# SimpleSwitch.net
KiCad netlist of a schematic drawn in EAGLE
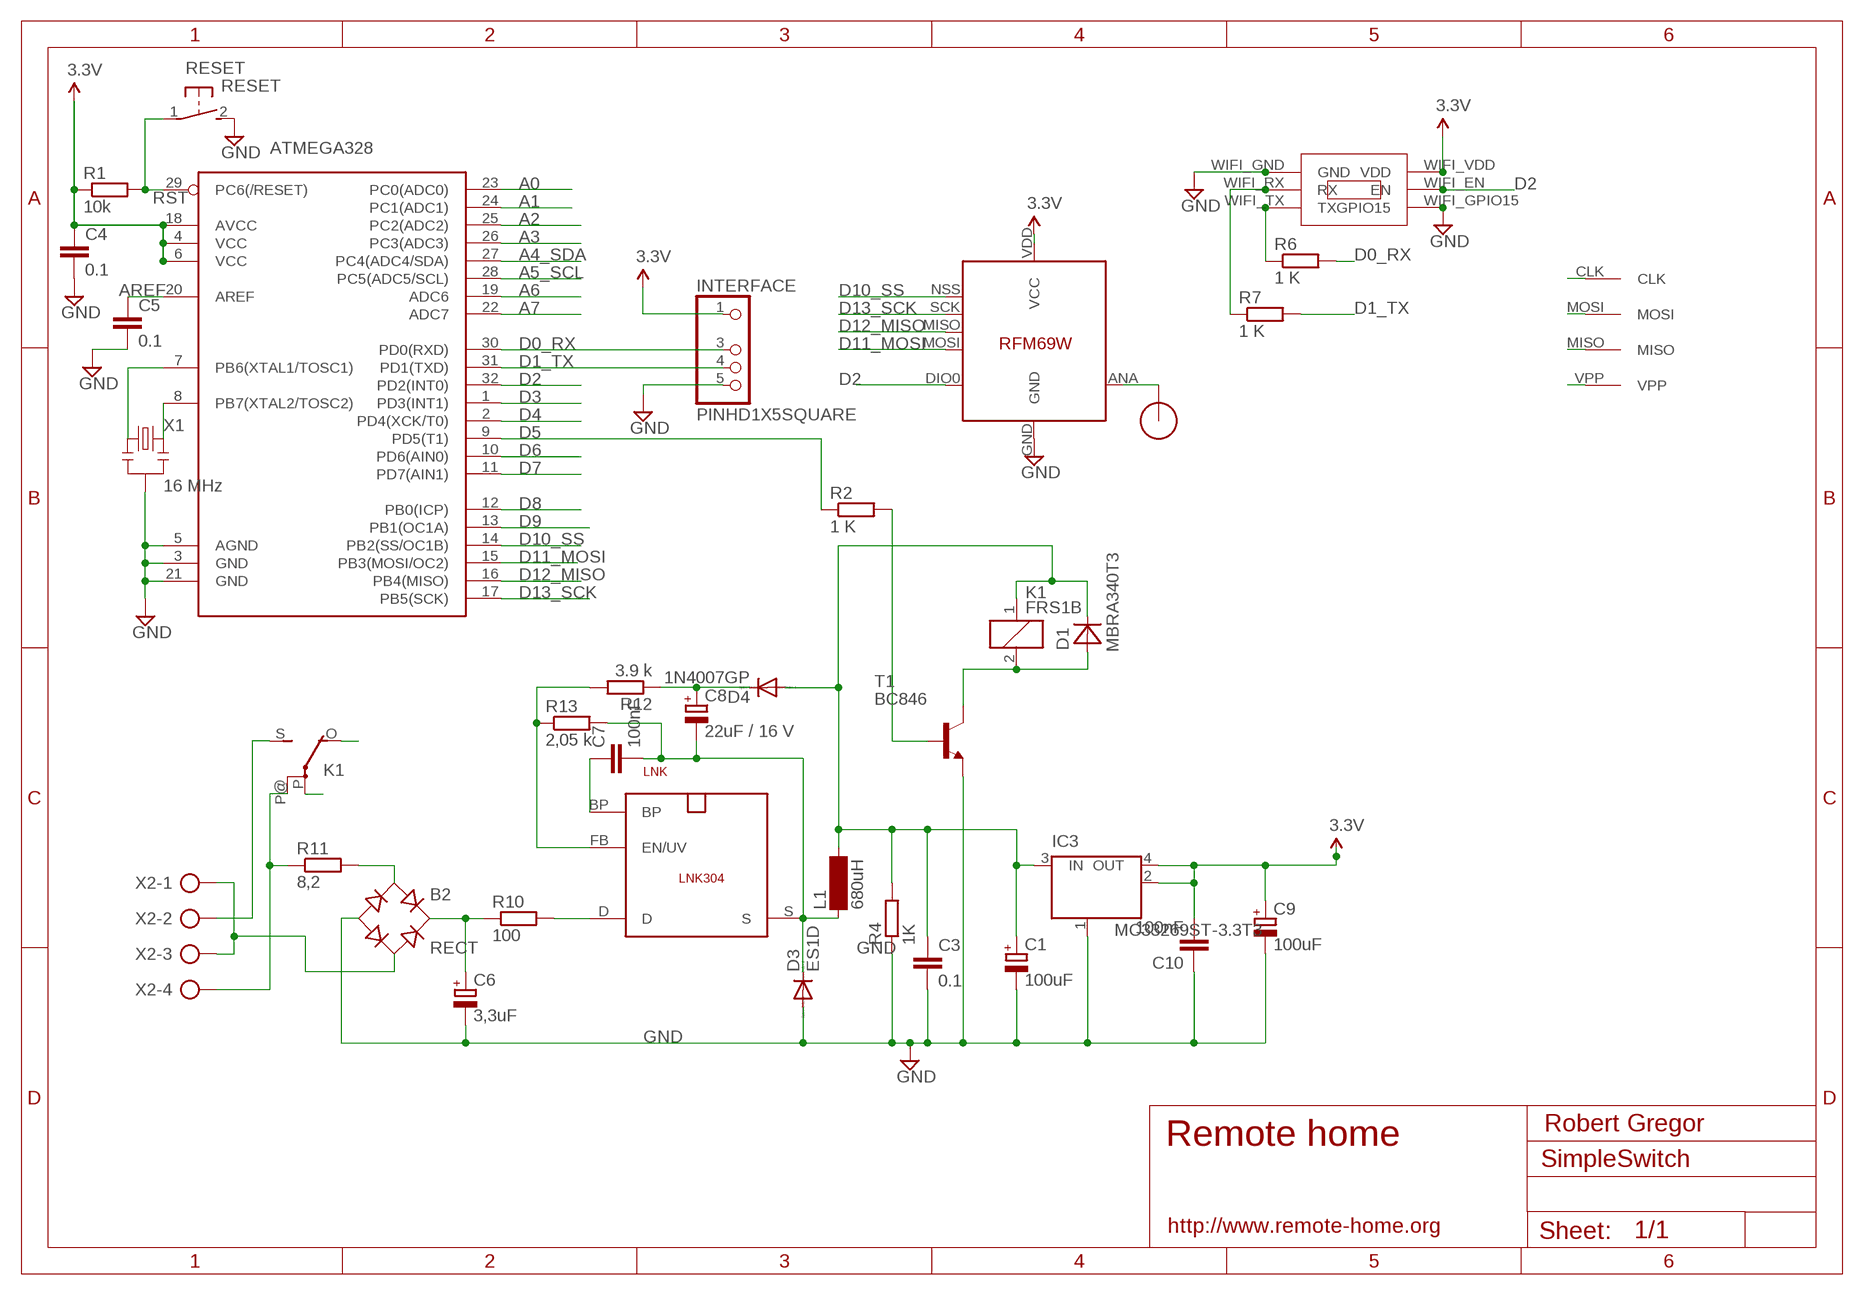
[diagram p0: schematic, sheet 1]

(export (version "E")
  (design (tool "Eeschema 10.0.6"))
  (components
    (comp (ref "ATMEGA328")
      (value "ATMega-328")
      (footprint "eagle-import:TQFP32-08")
      (libsource (lib "eagle-import") (part "ATMEGA168/328TQFP32"))
    )
    (comp (ref "B2")
      (value "RECT")
      (footprint "eagle-import:TO-269AA")
      (libsource (lib "eagle-import") (part "RECTIFIER-S40"))
    )
    (comp (ref "C1")
      (value "100uF")
      (footprint "eagle-import:SMC_B")
      (libsource (lib "eagle-import") (part "CPOL-EUSMCB"))
    )
    (comp (ref "C3")
      (value "0.1")
      (footprint "eagle-import:C2012")
      (libsource (lib "eagle-import") (part "C-EUC2012"))
    )
    (comp (ref "C4")
      (value "0.1")
      (footprint "eagle-import:C2012")
      (libsource (lib "eagle-import") (part "C-EUC2012"))
    )
    (comp (ref "C5")
      (value "0.1")
      (footprint "eagle-import:C2012")
      (libsource (lib "eagle-import") (part "C-EUC2012"))
    )
    (comp (ref "C6")
      (value "3,3uF")
      (footprint "eagle-import:E5-10,5")
      (libsource (lib "eagle-import") (part "CPOL-EUE5-10.5"))
    )
    (comp (ref "C7")
      (value "100nF")
      (footprint "eagle-import:C2012")
      (libsource (lib "eagle-import") (part "C-EUC2012"))
    )
    (comp (ref "C8")
      (value "22uF / 16 V")
      (footprint "eagle-import:SMC_C")
      (libsource (lib "eagle-import") (part "CPOL-EUSMCC"))
    )
    (comp (ref "C9")
      (value "100uF")
      (footprint "eagle-import:SMC_B")
      (libsource (lib "eagle-import") (part "CPOL-EUSMCB"))
    )
    (comp (ref "C10")
      (value "100nF")
      (footprint "eagle-import:C2012")
      (libsource (lib "eagle-import") (part "C-EUC2012"))
    )
    (comp (ref "D1")
      (value "MBRA340T3")
      (footprint "eagle-import:SMA")
      (libsource (lib "eagle-import") (part "MBRA340T3"))
    )
    (comp (ref "D3")
      (value "ES1D")
      (footprint "eagle-import:DO214AC")
      (libsource (lib "eagle-import") (part "DIODE-DO214AC"))
    )
    (comp (ref "D4")
      (value "1N4007GP")
      (footprint "eagle-import:DO214AA")
      (libsource (lib "eagle-import") (part "DIODE-DO214AA"))
    )
    (comp (ref "IC3")
      (value "MC33269ST-3.3T3")
      (footprint "eagle-import:SOT223")
      (libsource (lib "eagle-import") (part "MC33269ST-3.3T3"))
    )
    (comp (ref "INTERFACE")
      (value "PINHD1X5SQUARE")
      (footprint "eagle-import:PINHD1X05-SQUARE")
      (libsource (lib "eagle-import") (part "PINHD1X5SQUARE"))
    )
    (comp (ref "K1")
      (value "FRS1B")
      (footprint "eagle-import:FRS1B")
      (libsource (lib "eagle-import") (part "FRS1B"))
    )
    (comp (ref "L1")
      (value "680uH")
      (footprint "eagle-import:BS11")
      (libsource (lib "eagle-import") (part "BS11"))
    )
    (comp (ref "LNK")
      (value "LNK304")
      (footprint "eagle-import:SO-8C")
      (libsource (lib "eagle-import") (part "SO-8C"))
    )
    (comp (ref "R1")
      (value "10k")
      (footprint "eagle-import:R2012")
      (libsource (lib "eagle-import") (part "R-EU_R2012"))
    )
    (comp (ref "R2")
      (value "1 K")
      (footprint "eagle-import:M2012")
      (libsource (lib "eagle-import") (part "R-EU_M2012"))
    )
    (comp (ref "R4")
      (value "1K")
      (footprint "eagle-import:M2012")
      (libsource (lib "eagle-import") (part "R-EU_M2012"))
    )
    (comp (ref "R6")
      (value "1 K")
      (footprint "eagle-import:M2012")
      (libsource (lib "eagle-import") (part "R-EU_M2012"))
    )
    (comp (ref "R7")
      (value "1 K")
      (footprint "eagle-import:M2012")
      (libsource (lib "eagle-import") (part "R-EU_M2012"))
    )
    (comp (ref "R10")
      (value "100")
      (footprint "eagle-import:R2512W")
      (libsource (lib "eagle-import") (part "R-EU_R2512W"))
    )
    (comp (ref "R11")
      (value "8,2")
      (footprint "eagle-import:0411_12")
      (libsource (lib "eagle-import") (part "R-EU_0411/12"))
    )
    (comp (ref "R12")
      (value "3.9 k")
      (footprint "eagle-import:M2012")
      (libsource (lib "eagle-import") (part "R-EU_M2012"))
    )
    (comp (ref "R13")
      (value "2,05 k")
      (footprint "eagle-import:M2012")
      (libsource (lib "eagle-import") (part "R-EU_M2012"))
    )
    (comp (ref "RESET")
      (value "RESET")
      (footprint "eagle-import:DTSM-3")
      (libsource (lib "eagle-import") (part "DTSM-3"))
    )
    (comp (ref "RFM69")
      (value "RFM69W")
      (footprint "eagle-import:RFM69W")
      (libsource (lib "eagle-import") (part "RFM69W"))
    )
    (comp (ref "T1")
      (value "BC846")
      (footprint "eagle-import:SOT23")
      (libsource (lib "eagle-import") (part "BC846"))
    )
    (comp (ref "U$1")
      (value "RFM12B_ANTENNA")
      (footprint "eagle-import:RFM12B-ANTENNA")
      (libsource (lib "eagle-import") (part "RFM12B_ANTENNA"))
    )
    (comp (ref "U$2")
      (value "AVRHEADERDIP")
      (footprint "eagle-import:AVRHEADER")
      (libsource (lib "eagle-import") (part "AVRHEADERDIP"))
    )
    (comp (ref "U$5")
      (value "ESP03")
      (footprint "eagle-import:ESP03")
      (libsource (lib "eagle-import") (part "ESP03"))
    )
    (comp (ref "X1")
      (value "16 MHz")
      (footprint "eagle-import:RESONATOR-SMD")
      (libsource (lib "eagle-import") (part "RESONATORSMD"))
    )
    (comp (ref "X2")
      (value "AK500/4")
      (footprint "eagle-import:AK500_4")
      (libsource (lib "eagle-import") (part "AK500/4"))
    )
  )
  (nets
    (net (code "1") (name "/A0") (class "Default")
      (node (ref "ATMEGA328") (pin "23") (pinfunction "PC0(ADC0)_23") (pintype "bidirectional"))
    )
    (net (code "2") (name "/A1") (class "Default")
      (node (ref "ATMEGA328") (pin "24") (pinfunction "PC1(ADC1)_24") (pintype "bidirectional"))
    )
    (net (code "3") (name "/A2") (class "Default")
      (node (ref "ATMEGA328") (pin "25") (pinfunction "PC2(ADC2)_25") (pintype "bidirectional"))
    )
    (net (code "4") (name "/A3") (class "Default")
      (node (ref "ATMEGA328") (pin "26") (pinfunction "PC3(ADC3)_26") (pintype "bidirectional"))
    )
    (net (code "5") (name "/A4_SDA") (class "Default")
      (node (ref "ATMEGA328") (pin "27") (pinfunction "PC4(ADC4/SDA)_27") (pintype "bidirectional"))
    )
    (net (code "6") (name "/A5_SCL") (class "Default")
      (node (ref "ATMEGA328") (pin "28") (pinfunction "PC5(ADC5/SCL)_28") (pintype "bidirectional"))
    )
    (net (code "7") (name "/A6") (class "Default")
      (node (ref "ATMEGA328") (pin "19") (pinfunction "ADC6_19") (pintype "bidirectional"))
    )
    (net (code "8") (name "/A7") (class "Default")
      (node (ref "ATMEGA328") (pin "22") (pinfunction "ADC7_22") (pintype "bidirectional"))
    )
    (net (code "9") (name "/AREF") (class "Default")
      (node (ref "ATMEGA328") (pin "20") (pinfunction "AREF_20") (pintype "bidirectional"))
      (node (ref "C5") (pin "1") (pinfunction "1_1") (pintype "passive"))
    )
    (net (code "10") (name "/D0_RX") (class "Default")
      (node (ref "ATMEGA328") (pin "30") (pinfunction "PD0(RXD)_30") (pintype "bidirectional"))
      (node (ref "INTERFACE") (pin "3") (pinfunction "3_3") (pintype "passive"))
      (node (ref "R6") (pin "2") (pinfunction "2_2") (pintype "passive"))
    )
    (net (code "11") (name "/D1_TX") (class "Default")
      (node (ref "ATMEGA328") (pin "31") (pinfunction "PD1(TXD)_31") (pintype "bidirectional"))
      (node (ref "INTERFACE") (pin "4") (pinfunction "4_4") (pintype "passive"))
      (node (ref "R7") (pin "2") (pinfunction "2_2") (pintype "passive"))
    )
    (net (code "12") (name "/D2") (class "Default")
      (node (ref "ATMEGA328") (pin "32") (pinfunction "PD2(INT0)_32") (pintype "bidirectional"))
      (node (ref "RFM69") (pin "DIO0") (pinfunction "DIO0_DIO0") (pintype "open_collector"))
      (node (ref "U$5") (pin "WIFI_EN") (pinfunction "EN_WIFI_EN") (pintype "input"))
    )
    (net (code "13") (name "/D3") (class "Default")
      (node (ref "ATMEGA328") (pin "1") (pinfunction "PD3(INT1)_1") (pintype "bidirectional"))
    )
    (net (code "14") (name "/D4") (class "Default")
      (node (ref "ATMEGA328") (pin "2") (pinfunction "PD4(XCK/T0)_2") (pintype "bidirectional"))
    )
    (net (code "15") (name "/D5") (class "Default")
      (node (ref "ATMEGA328") (pin "9") (pinfunction "PD5(T1)_9") (pintype "bidirectional"))
      (node (ref "R2") (pin "1") (pinfunction "1_1") (pintype "passive"))
    )
    (net (code "16") (name "/D6") (class "Default")
      (node (ref "ATMEGA328") (pin "10") (pinfunction "PD6(AIN0)_10") (pintype "bidirectional"))
    )
    (net (code "17") (name "/D7") (class "Default")
      (node (ref "ATMEGA328") (pin "11") (pinfunction "PD7(AIN1)_11") (pintype "bidirectional"))
    )
    (net (code "18") (name "/D8") (class "Default")
      (node (ref "ATMEGA328") (pin "12") (pinfunction "PB0(ICP)_12") (pintype "bidirectional"))
    )
    (net (code "19") (name "/D9") (class "Default")
      (node (ref "ATMEGA328") (pin "13") (pinfunction "PB1(OC1A)_13") (pintype "bidirectional"))
    )
    (net (code "20") (name "/D10_SS") (class "Default")
      (node (ref "ATMEGA328") (pin "14") (pinfunction "PB2(SS/OC1B)_14") (pintype "bidirectional"))
      (node (ref "RFM69") (pin "NSS") (pinfunction "SEL_NSS") (pintype "input"))
    )
    (net (code "21") (name "/D11_MOSI") (class "Default")
      (node (ref "ATMEGA328") (pin "15") (pinfunction "PB3(MOSI/OC2)_15") (pintype "bidirectional"))
      (node (ref "RFM69") (pin "MOSI") (pinfunction "MOSI_MOSI") (pintype "output"))
      (node (ref "U$2") (pin "MOSI") (pinfunction "MOSI_MOSI") (pintype "bidirectional"))
    )
    (net (code "22") (name "/D12_MISO") (class "Default")
      (node (ref "ATMEGA328") (pin "16") (pinfunction "PB4(MISO)_16") (pintype "bidirectional"))
      (node (ref "RFM69") (pin "MISO") (pinfunction "MISO_MISO") (pintype "input"))
      (node (ref "U$2") (pin "MISO") (pinfunction "MISO_MISO") (pintype "bidirectional"))
    )
    (net (code "23") (name "/D13_SCK") (class "Default")
      (node (ref "ATMEGA328") (pin "17") (pinfunction "PB5(SCK)_17") (pintype "bidirectional"))
      (node (ref "RFM69") (pin "SCK") (pinfunction "SCK_SCK") (pintype "input"))
      (node (ref "U$2") (pin "CLK") (pinfunction "CLK_CLK") (pintype "bidirectional"))
    )
    (net (code "24") (name "/RST") (class "Default")
      (node (ref "ATMEGA328") (pin "29") (pinfunction "PC6(/RESET)_29") (pintype "bidirectional"))
      (node (ref "R1") (pin "2") (pinfunction "2_2") (pintype "passive"))
      (node (ref "RESET") (pin "1") (pinfunction "1_1") (pintype "passive"))
      (node (ref "U$2") (pin "VPP") (pinfunction "VPP_VPP") (pintype "bidirectional"))
    )
    (net (code "25") (name "3.3V") (class "Default")
      (node (ref "ATMEGA328") (pin "18") (pinfunction "AVCC_18") (pintype "bidirectional"))
      (node (ref "ATMEGA328") (pin "4") (pinfunction "VCC_4") (pintype "bidirectional"))
      (node (ref "ATMEGA328") (pin "6") (pinfunction "VCC_6") (pintype "bidirectional"))
      (node (ref "C10") (pin "2") (pinfunction "2_2") (pintype "passive"))
      (node (ref "C4") (pin "1") (pinfunction "1_1") (pintype "passive"))
      (node (ref "C9") (pin "+") (pinfunction "+_+") (pintype "passive"))
      (node (ref "IC3") (pin "2") (pinfunction "OUT_2") (pintype "passive"))
      (node (ref "IC3") (pin "4") (pinfunction "OUT_4") (pintype "passive"))
      (node (ref "INTERFACE") (pin "1") (pinfunction "1_1") (pintype "passive"))
      (node (ref "R1") (pin "1") (pinfunction "1_1") (pintype "passive"))
      (node (ref "RFM69") (pin "VDD") (pinfunction "VCC_VDD") (pintype "power_in"))
      (node (ref "U$5") (pin "WIFI_VDD") (pinfunction "VDD_WIFI_VDD") (pintype "power_in"))
    )
    (net (code "26") (name "GND") (class "Default")
      (node (ref "ATMEGA328") (pin "21") (pinfunction "GND_21") (pintype "bidirectional"))
      (node (ref "ATMEGA328") (pin "3") (pinfunction "GND_3") (pintype "bidirectional"))
      (node (ref "ATMEGA328") (pin "5") (pinfunction "AGND_5") (pintype "bidirectional"))
      (node (ref "B2") (pin "-") (pinfunction "-_-") (pintype "passive"))
      (node (ref "C1") (pin "-") (pinfunction "-_-") (pintype "passive"))
      (node (ref "C10") (pin "1") (pinfunction "1_1") (pintype "passive"))
      (node (ref "C3") (pin "2") (pinfunction "2_2") (pintype "passive"))
      (node (ref "C4") (pin "2") (pinfunction "2_2") (pintype "passive"))
      (node (ref "C5") (pin "2") (pinfunction "2_2") (pintype "passive"))
      (node (ref "C6") (pin "-") (pinfunction "-_-") (pintype "passive"))
      (node (ref "C9") (pin "-") (pinfunction "-_-") (pintype "passive"))
      (node (ref "D3") (pin "A") (pinfunction "A_A") (pintype "passive"))
      (node (ref "IC3") (pin "1") (pinfunction "GND/ADJ_1") (pintype "input"))
      (node (ref "INTERFACE") (pin "5") (pinfunction "5_5") (pintype "passive"))
      (node (ref "R4") (pin "1") (pinfunction "1_1") (pintype "passive"))
      (node (ref "RESET") (pin "2") (pinfunction "2_2") (pintype "passive"))
      (node (ref "RFM69") (pin "GND") (pinfunction "GND_GND") (pintype "power_in"))
      (node (ref "T1") (pin "2") (pinfunction "E_2") (pintype "passive"))
      (node (ref "U$5") (pin "WIFI_GND") (pinfunction "GND_WIFI_GND") (pintype "power_in"))
      (node (ref "U$5") (pin "WIFI_GPIO15") (pinfunction "GPIO15_WIFI_GPIO15") (pintype "input"))
      (node (ref "X1") (pin "2") (pinfunction "2_2") (pintype "passive"))
    )
    (net (code "27") (name "Net-(ATMEGA328-PB6(XTAL1{slash}TOSC1))") (class "Default")
      (node (ref "ATMEGA328") (pin "7") (pinfunction "PB6(XTAL1/TOSC1)_7") (pintype "bidirectional"))
      (node (ref "X1") (pin "1") (pinfunction "1_1") (pintype "passive"))
    )
    (net (code "28") (name "Net-(ATMEGA328-PB7(XTAL2{slash}TOSC2))") (class "Default")
      (node (ref "ATMEGA328") (pin "8") (pinfunction "PB7(XTAL2/TOSC2)_8") (pintype "bidirectional"))
      (node (ref "X1") (pin "3") (pinfunction "3_3") (pintype "passive"))
    )
    (net (code "29") (name "Net-(B2-Pad+)") (class "Default")
      (node (ref "B2") (pin "+") (pinfunction "+_+") (pintype "passive"))
      (node (ref "C6") (pin "+") (pinfunction "+_+") (pintype "passive"))
      (node (ref "R10") (pin "1") (pinfunction "1_1") (pintype "passive"))
    )
    (net (code "30") (name "Net-(B2-PadAC1)") (class "Default")
      (node (ref "B2") (pin "AC1") (pinfunction "AC1_AC1") (pintype "passive"))
      (node (ref "R11") (pin "2") (pinfunction "2_2") (pintype "passive"))
    )
    (net (code "31") (name "Net-(C7-Pad1)") (class "Default")
      (node (ref "C7") (pin "1") (pinfunction "1_1") (pintype "passive"))
      (node (ref "LNK") (pin "BP") (pinfunction "BP_BP") (pintype "passive"))
    )
    (net (code "32") (name "Net-(C7-Pad2)") (class "Default")
      (node (ref "C7") (pin "2") (pinfunction "2_2") (pintype "passive"))
      (node (ref "C8") (pin "-") (pinfunction "-_-") (pintype "passive"))
      (node (ref "D3") (pin "C") (pinfunction "C_C") (pintype "passive"))
      (node (ref "L1") (pin "1") (pinfunction "1_1") (pintype "passive"))
      (node (ref "LNK") (pin "S") (pinfunction "S_S") (pintype "power_in"))
      (node (ref "R13") (pin "2") (pinfunction "2_2") (pintype "passive"))
    )
    (net (code "33") (name "Net-(C8-Pad+)") (class "Default")
      (node (ref "C8") (pin "+") (pinfunction "+_+") (pintype "passive"))
      (node (ref "D4") (pin "C") (pinfunction "C_C") (pintype "passive"))
      (node (ref "R12") (pin "1") (pinfunction "1_1") (pintype "passive"))
    )
    (net (code "34") (name "Net-(IC3-IN)") (class "Default")
      (node (ref "C1") (pin "+") (pinfunction "+_+") (pintype "passive"))
      (node (ref "C3") (pin "1") (pinfunction "1_1") (pintype "passive"))
      (node (ref "D1") (pin "C") (pinfunction "C_C") (pintype "passive"))
      (node (ref "D4") (pin "A") (pinfunction "A_A") (pintype "passive"))
      (node (ref "IC3") (pin "3") (pinfunction "IN_3") (pintype "input"))
      (node (ref "K1") (pin "1") (pinfunction "1_1") (pintype "passive"))
      (node (ref "L1") (pin "2") (pinfunction "2_2") (pintype "passive"))
      (node (ref "R4") (pin "2") (pinfunction "2_2") (pintype "passive"))
    )
    (net (code "35") (name "Net-(LNK-EN{slash}UV)") (class "Default")
      (node (ref "LNK") (pin "FB") (pinfunction "EN/UV_FB") (pintype "input"))
      (node (ref "R12") (pin "2") (pinfunction "2_2") (pintype "passive"))
      (node (ref "R13") (pin "1") (pinfunction "1_1") (pintype "passive"))
    )
    (net (code "36") (name "Net-(LNK-PadD)") (class "Default")
      (node (ref "LNK") (pin "D") (pinfunction "D_D") (pintype "open_collector"))
      (node (ref "R10") (pin "2") (pinfunction "2_2") (pintype "passive"))
    )
    (net (code "37") (name "Net-(RFM69-ANT)") (class "Default")
      (node (ref "RFM69") (pin "ANA") (pinfunction "ANT_ANA") (pintype "passive"))
      (node (ref "U$1") (pin "P$1") (pinfunction "1_P$1") (pintype "bidirectional"))
    )
    (net (code "38") (name "Net-(T1-B)") (class "Default")
      (node (ref "R2") (pin "2") (pinfunction "2_2") (pintype "passive"))
      (node (ref "T1") (pin "1") (pinfunction "B_1") (pintype "passive"))
    )
    (net (code "39") (name "Net-(T1-C)") (class "Default")
      (node (ref "D1") (pin "A") (pinfunction "A_A") (pintype "passive"))
      (node (ref "K1") (pin "2") (pinfunction "2_2") (pintype "passive"))
      (node (ref "T1") (pin "3") (pinfunction "C_3") (pintype "passive"))
    )
    (net (code "40") (name "Net-(U$5-RX)") (class "Default")
      (node (ref "R7") (pin "1") (pinfunction "1_1") (pintype "passive"))
      (node (ref "U$5") (pin "WIFI_RX") (pinfunction "RX_WIFI_RX") (pintype "input"))
    )
    (net (code "41") (name "Net-(U$5-TX)") (class "Default")
      (node (ref "R6") (pin "1") (pinfunction "1_1") (pintype "passive"))
      (node (ref "U$5") (pin "WIFI_TX") (pinfunction "TX_WIFI_TX") (pintype "output"))
    )
    (net (code "42") (name "Net-(X2A-KL)") (class "Default")
      (node (ref "B2") (pin "AC2") (pinfunction "AC2_AC2") (pintype "passive"))
      (node (ref "X2") (pin "1") (pinfunction "KL_1") (pintype "passive"))
      (node (ref "X2") (pin "3") (pinfunction "KL_3") (pintype "passive"))
    )
    (net (code "43") (name "Net-(X2B-KL)") (class "Default")
      (node (ref "K1") (pin "S") (pinfunction "S_S") (pintype "passive"))
      (node (ref "X2") (pin "2") (pinfunction "KL_2") (pintype "passive"))
    )
    (net (code "44") (name "Net-(X2D-KL)") (class "Default")
      (node (ref "K1") (pin "P@") (pinfunction "P_P@") (pintype "passive"))
      (node (ref "R11") (pin "1") (pinfunction "1_1") (pintype "passive"))
      (node (ref "X2") (pin "4") (pinfunction "KL_4") (pintype "passive"))
    )
    (net (code "45") (name "unconnected-(K1-PadO)") (class "Default")
      (node (ref "K1") (pin "O") (pinfunction "O_O") (pintype "passive"))
    )
    (net (code "46") (name "unconnected-(K1-PadP)") (class "Default")
      (node (ref "K1") (pin "P") (pinfunction "P_P") (pintype "passive"))
    )
  )
)
